# POWERMUX.net
KiCad netlist of a schematic drawn in Altium Designer
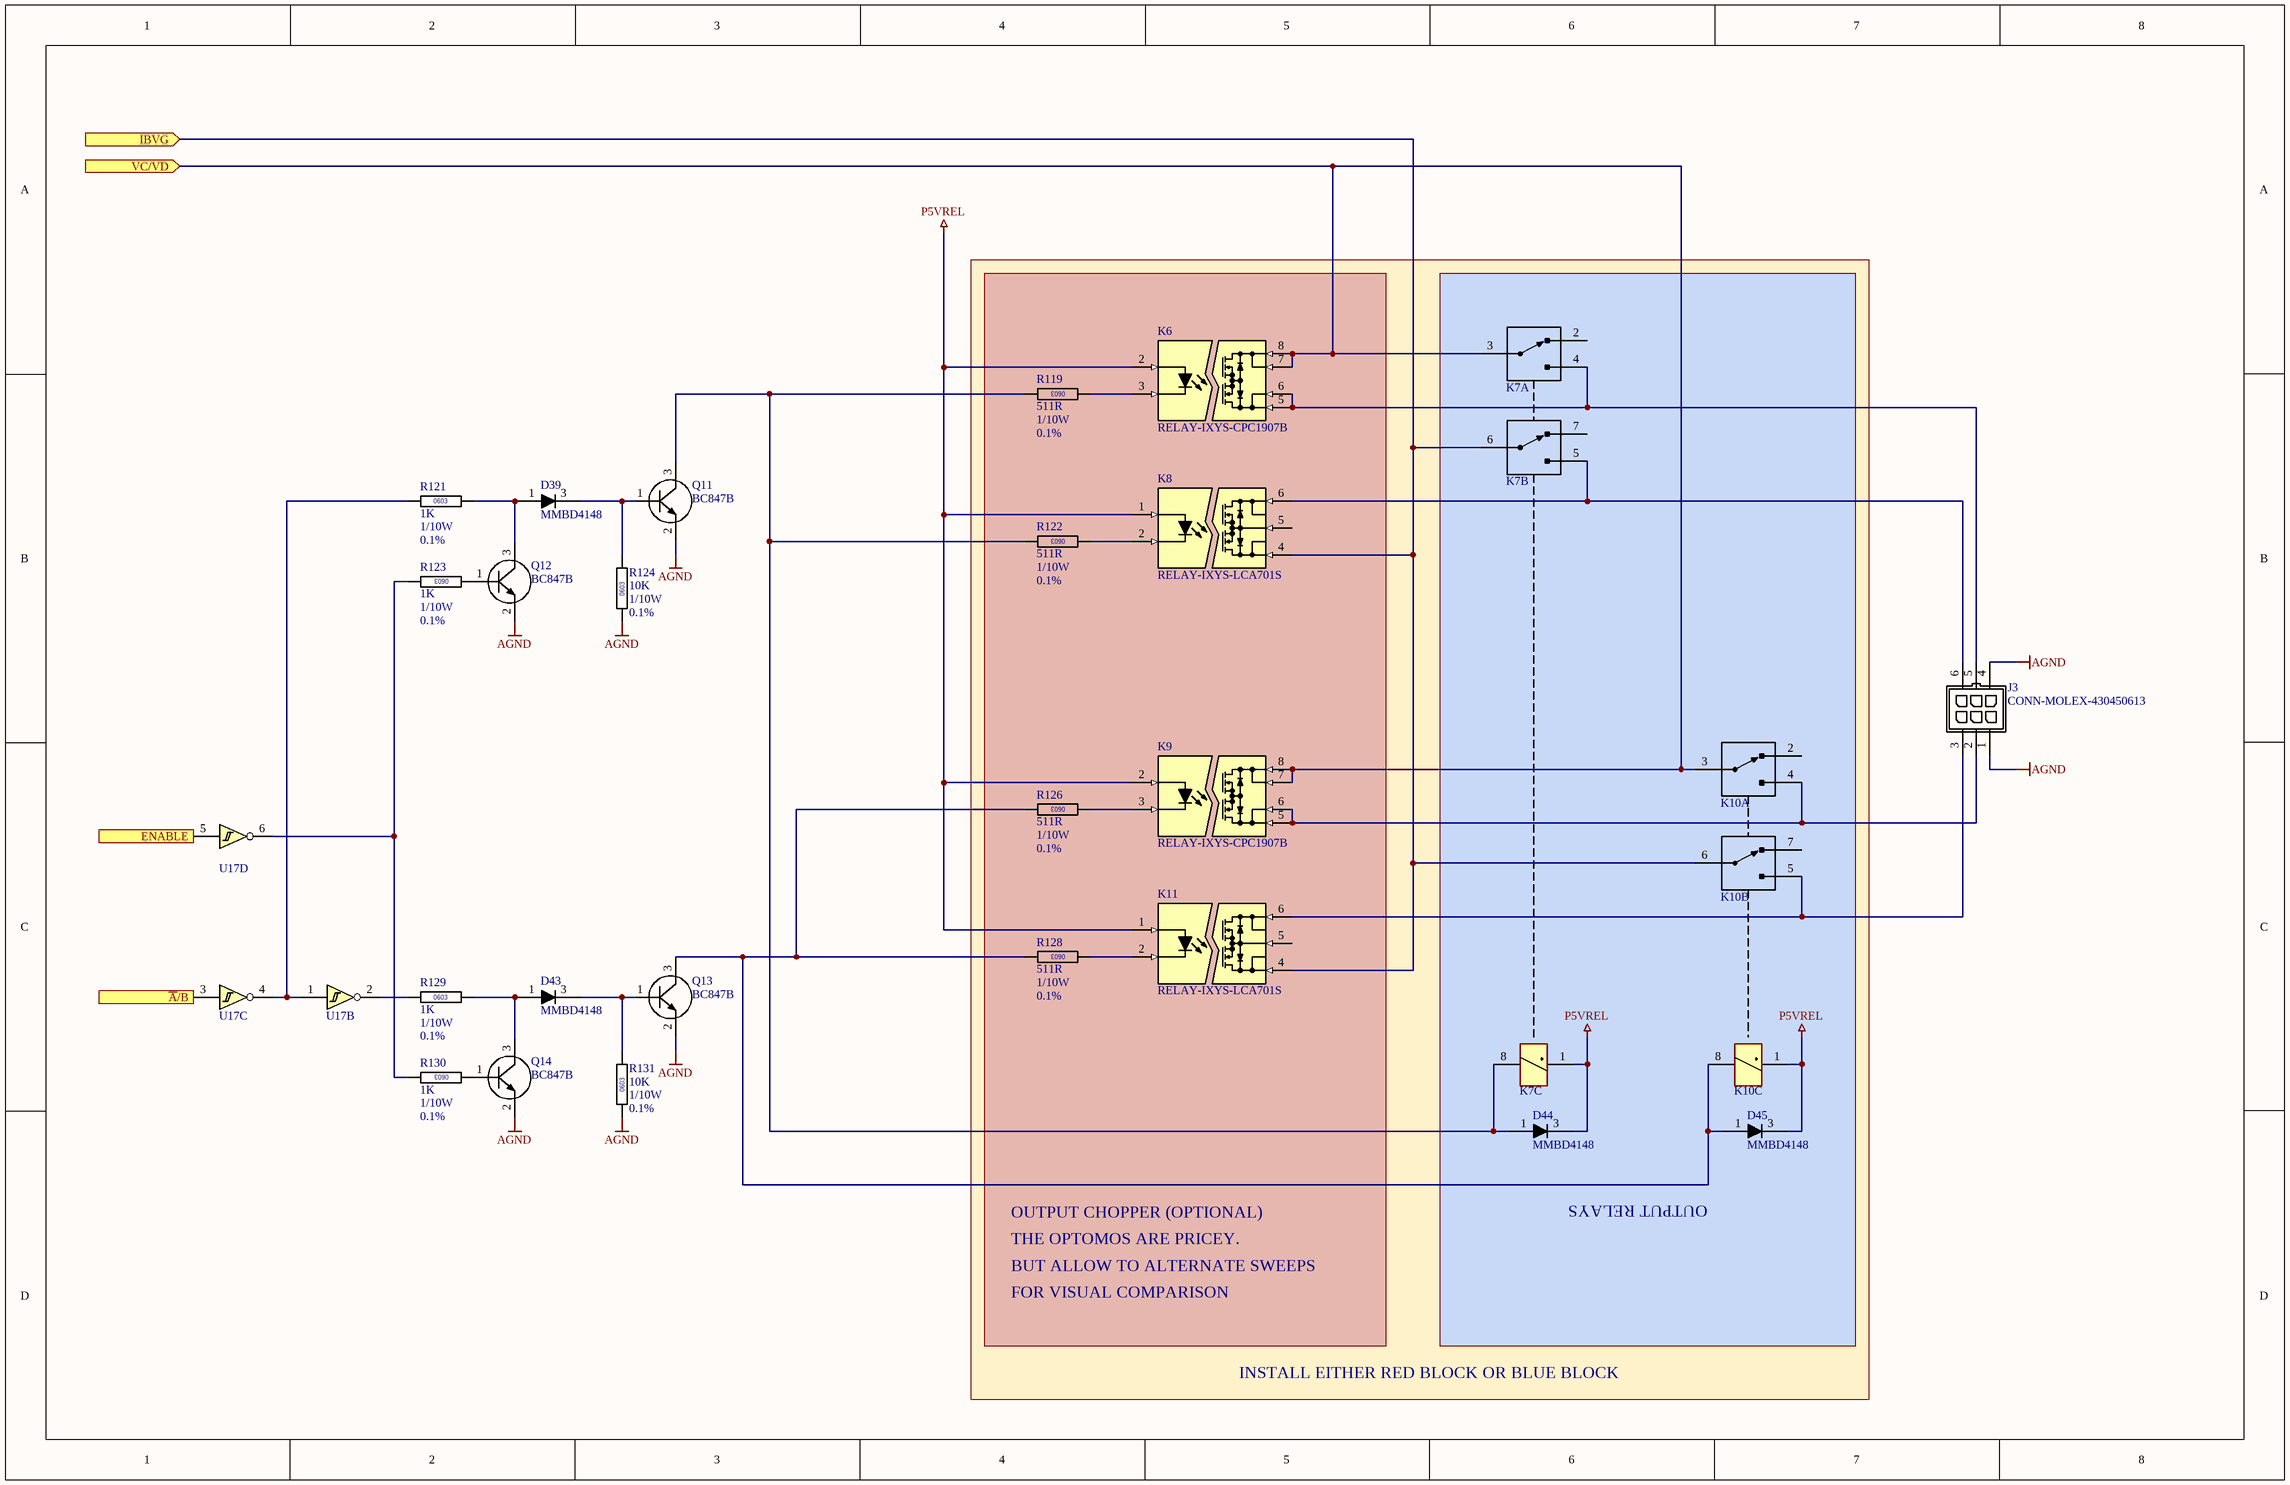
[diagram p0: POWERMUX.SchDoc]

(export (version "E")
  (design (tool "Eeschema 10.0.6"))
  (components
    (comp (ref "D39")
      (value "MMBD4148")
      (description "DIODE,RECTIFIER,75V,0.3A,MMBD4148,SOT23")
      (libsource (lib "DIODES") (part "DIODE-RECTIFIER-DIODES-MMBD4148-SOT23"))
    )
    (comp (ref "D43")
      (value "MMBD4148")
      (description "DIODE,RECTIFIER,75V,0.3A,MMBD4148,SOT23")
      (libsource (lib "DIODES") (part "DIODE-RECTIFIER-DIODES-MMBD4148-SOT23"))
    )
    (comp (ref "D44")
      (value "MMBD4148")
      (description "DIODE,RECTIFIER,75V,0.3A,MMBD4148,SOT23")
      (libsource (lib "DIODES") (part "DIODE-RECTIFIER-DIODES-MMBD4148-SOT23"))
    )
    (comp (ref "D45")
      (value "MMBD4148")
      (description "DIODE,RECTIFIER,75V,0.3A,MMBD4148,SOT23")
      (libsource (lib "DIODES") (part "DIODE-RECTIFIER-DIODES-MMBD4148-SOT23"))
    )
    (comp (ref "J3")
      (value "CONN-MOLEX-430450613")
      (footprint "CONN-MOLEX-430450613")
      (description "CONN,2X3,MOLEX MICROFIT,TH,VERT")
      (libsource (lib "CONNECTORS") (part "CONN-MOLEX-430450613"))
    )
    (comp (ref "K6")
      (value "RELAY-IXYS-CPC1907B")
      (footprint "SO508P1676-8N")
      (description "RELAY,OPTOMOS,6A,60V,AC,IXYS,CPC1907B,SMD")
      (libsource (lib "RELAYS") (part "RELAY-IXYS-CPC1907B"))
    )
    (comp (ref "K7")
      (value "RELAY-KEMET-UA2-5NJ")
      (footprint "RELAY-KEMET-UA2-5NJ")
      (description "RELAY,DPDT,1A,250VAC,220VDC,5V COIL,KEMET,UA2-5NJ")
      (libsource (lib "RELAYS") (part "RELAY-KEMET-UA2-5NJ"))
    )
    (comp (ref "K8")
      (value "RELAY-IXYS-LCA701S")
      (footprint "SO254P960-6N")
      (description "RELAY,OPTOMOS,1.5A,100V,AC,IXYS,LCA701S,SMD")
      (libsource (lib "RELAYS") (part "RELAY-IXYS-LCA701S"))
    )
    (comp (ref "K9")
      (value "RELAY-IXYS-CPC1907B")
      (footprint "SO508P1676-8N")
      (description "RELAY,OPTOMOS,6A,60V,AC,IXYS,CPC1907B,SMD")
      (libsource (lib "RELAYS") (part "RELAY-IXYS-CPC1907B"))
    )
    (comp (ref "K10")
      (value "RELAY-KEMET-UA2-5NJ")
      (footprint "RELAY-KEMET-UA2-5NJ")
      (description "RELAY,DPDT,1A,250VAC,220VDC,5V COIL,KEMET,UA2-5NJ")
      (libsource (lib "RELAYS") (part "RELAY-KEMET-UA2-5NJ"))
    )
    (comp (ref "K11")
      (value "RELAY-IXYS-LCA701S")
      (footprint "SO254P960-6N")
      (description "RELAY,OPTOMOS,1.5A,100V,AC,IXYS,LCA701S,SMD")
      (libsource (lib "RELAYS") (part "RELAY-IXYS-LCA701S"))
    )
    (comp (ref "Q11")
      (value "BC847B")
      (footprint "SOT23")
      (description "XSTR,NPN,45V,0.1A,,BC847B,SOT23")
      (libsource (lib "TRANSISTORS") (part "XSTR-NPN-BC847"))
    )
    (comp (ref "Q12")
      (value "BC847B")
      (footprint "SOT23")
      (description "XSTR,NPN,45V,0.1A,,BC847B,SOT23")
      (libsource (lib "TRANSISTORS") (part "XSTR-NPN-BC847"))
    )
    (comp (ref "Q13")
      (value "BC847B")
      (footprint "SOT23")
      (description "XSTR,NPN,45V,0.1A,,BC847B,SOT23")
      (libsource (lib "TRANSISTORS") (part "XSTR-NPN-BC847"))
    )
    (comp (ref "Q14")
      (value "BC847B")
      (footprint "SOT23")
      (description "XSTR,NPN,45V,0.1A,,BC847B,SOT23")
      (libsource (lib "TRANSISTORS") (part "XSTR-NPN-BC847"))
    )
    (comp (ref "R119")
      (value "511R")
      (footprint "RESC0603")
      (description "RESISTOR,511R,0.1%,100mW,0603 (1608)")
      (fields
        (field (name "POWER") "1/10W")
        (field (name "TOLERANCE") "0.1%")
        (field (name "Comment") "RESC0603")
      )
      (libsource (lib "RESISTORS") (part "RESC-0603-511R-0.1%-1/10W"))
    )
    (comp (ref "R121")
      (value "1K")
      (footprint "RESC0603")
      (description "RESISTOR,1K,0.1%,100mW,0603 (1608)")
      (fields
        (field (name "POWER") "1/10W")
        (field (name "TOLERANCE") "0.1%")
        (field (name "Comment") "RESC0603")
      )
      (libsource (lib "RESISTORS") (part "RESC-0603-1K-0.1%-1/10W"))
    )
    (comp (ref "R122")
      (value "511R")
      (footprint "RESC0603")
      (description "RESISTOR,511R,0.1%,100mW,0603 (1608)")
      (fields
        (field (name "POWER") "1/10W")
        (field (name "TOLERANCE") "0.1%")
        (field (name "Comment") "RESC0603")
      )
      (libsource (lib "RESISTORS") (part "RESC-0603-511R-0.1%-1/10W"))
    )
    (comp (ref "R123")
      (value "1K")
      (footprint "RESC0603")
      (description "RESISTOR,1K,0.1%,100mW,0603 (1608)")
      (fields
        (field (name "POWER") "1/10W")
        (field (name "TOLERANCE") "0.1%")
        (field (name "Comment") "RESC0603")
      )
      (libsource (lib "RESISTORS") (part "RESC-0603-1K-0.1%-1/10W"))
    )
    (comp (ref "R124")
      (value "10K")
      (footprint "RESC0603")
      (description "RESISTOR,10K,0.1%,100mW,0603 (1608)")
      (fields
        (field (name "POWER") "1/10W")
        (field (name "TOLERANCE") "0.1%")
        (field (name "Comment") "RESC0603")
      )
      (libsource (lib "RESISTORS") (part "RESC-0603-10K-0.1%-1/10W"))
    )
    (comp (ref "R126")
      (value "511R")
      (footprint "RESC0603")
      (description "RESISTOR,511R,0.1%,100mW,0603 (1608)")
      (fields
        (field (name "POWER") "1/10W")
        (field (name "TOLERANCE") "0.1%")
        (field (name "Comment") "RESC0603")
      )
      (libsource (lib "RESISTORS") (part "RESC-0603-511R-0.1%-1/10W"))
    )
    (comp (ref "R128")
      (value "511R")
      (footprint "RESC0603")
      (description "RESISTOR,511R,0.1%,100mW,0603 (1608)")
      (fields
        (field (name "POWER") "1/10W")
        (field (name "TOLERANCE") "0.1%")
        (field (name "Comment") "RESC0603")
      )
      (libsource (lib "RESISTORS") (part "RESC-0603-511R-0.1%-1/10W"))
    )
    (comp (ref "R129")
      (value "1K")
      (footprint "RESC0603")
      (description "RESISTOR,1K,0.1%,100mW,0603 (1608)")
      (fields
        (field (name "POWER") "1/10W")
        (field (name "TOLERANCE") "0.1%")
        (field (name "Comment") "RESC0603")
      )
      (libsource (lib "RESISTORS") (part "RESC-0603-1K-0.1%-1/10W"))
    )
    (comp (ref "R130")
      (value "1K")
      (footprint "RESC0603")
      (description "RESISTOR,1K,0.1%,100mW,0603 (1608)")
      (fields
        (field (name "POWER") "1/10W")
        (field (name "TOLERANCE") "0.1%")
        (field (name "Comment") "RESC0603")
      )
      (libsource (lib "RESISTORS") (part "RESC-0603-1K-0.1%-1/10W"))
    )
    (comp (ref "R131")
      (value "10K")
      (footprint "RESC0603")
      (description "RESISTOR,10K,0.1%,100mW,0603 (1608)")
      (fields
        (field (name "POWER") "1/10W")
        (field (name "TOLERANCE") "0.1%")
        (field (name "Comment") "RESC0603")
      )
      (libsource (lib "RESISTORS") (part "RESC-0603-10K-0.1%-1/10W"))
    )
    (comp (ref "U17")
      (value "IC-TI-74HC14")
      (footprint "SOT23-6")
      (description "IC,NOT,HEX,SCHMITTTRIGGER,ONSEMI,MC74AC14DR2G,SO14")
      (libsource (lib "IC-74XX") (part "IC-TI-74HC14-SO14"))
    )
  )
  (nets
    (net (code "1") (name "/ENABLE") (class "Default")
      (node (ref "U17") (pin "5") (pinfunction "5_5") (pintype "passive"))
    )
    (net (code "2") (name "/IBVG") (class "Default")
      (node (ref "K10") (pin "6") (pinfunction "COM_6") (pintype "passive"))
      (node (ref "K11") (pin "4") (pinfunction "4_4") (pintype "input"))
      (node (ref "K7") (pin "6") (pinfunction "COM_6") (pintype "passive"))
      (node (ref "K8") (pin "4") (pinfunction "4_4") (pintype "input"))
    )
    (net (code "3") (name "/VC{slash}VD") (class "Default")
      (node (ref "K10") (pin "3") (pinfunction "COM_3") (pintype "passive"))
      (node (ref "K6") (pin "7") (pinfunction "7_7") (pintype "input"))
      (node (ref "K6") (pin "8") (pinfunction "8_8") (pintype "input"))
      (node (ref "K7") (pin "3") (pinfunction "COM_3") (pintype "passive"))
      (node (ref "K9") (pin "7") (pinfunction "7_7") (pintype "input"))
      (node (ref "K9") (pin "8") (pinfunction "8_8") (pintype "input"))
    )
    (net (code "4") (name "/~{A}{slash}B") (class "Default")
      (node (ref "U17") (pin "3") (pinfunction "3_3") (pintype "passive"))
    )
    (net (code "5") (name "AGND") (class "Default")
      (node (ref "J3") (pin "1") (pinfunction "1_1") (pintype "passive"))
      (node (ref "J3") (pin "4") (pinfunction "4_4") (pintype "passive"))
      (node (ref "Q11") (pin "2") (pinfunction "E_2") (pintype "passive"))
      (node (ref "Q12") (pin "2") (pinfunction "E_2") (pintype "passive"))
      (node (ref "Q13") (pin "2") (pinfunction "E_2") (pintype "passive"))
      (node (ref "Q14") (pin "2") (pinfunction "E_2") (pintype "passive"))
      (node (ref "R124") (pin "2") (pintype "passive"))
      (node (ref "R131") (pin "2") (pintype "passive"))
    )
    (net (code "6") (name "Net-(D39-A)") (class "Default")
      (node (ref "D39") (pin "1") (pinfunction "A_1") (pintype "passive"))
      (node (ref "Q12") (pin "3") (pinfunction "C_3") (pintype "passive"))
      (node (ref "R121") (pin "1") (pintype "passive"))
    )
    (net (code "7") (name "Net-(D39-K)") (class "Default")
      (node (ref "D39") (pin "3") (pinfunction "K_3") (pintype "passive"))
      (node (ref "Q11") (pin "1") (pinfunction "B_1") (pintype "passive"))
      (node (ref "R124") (pin "1") (pintype "passive"))
    )
    (net (code "8") (name "Net-(D43-A)") (class "Default")
      (node (ref "D43") (pin "1") (pinfunction "A_1") (pintype "passive"))
      (node (ref "Q14") (pin "3") (pinfunction "C_3") (pintype "passive"))
      (node (ref "R129") (pin "1") (pintype "passive"))
    )
    (net (code "9") (name "Net-(D43-K)") (class "Default")
      (node (ref "D43") (pin "3") (pinfunction "K_3") (pintype "passive"))
      (node (ref "Q13") (pin "1") (pinfunction "B_1") (pintype "passive"))
      (node (ref "R131") (pin "1") (pintype "passive"))
    )
    (net (code "10") (name "Net-(D44-A)") (class "Default")
      (node (ref "D44") (pin "1") (pinfunction "A_1") (pintype "passive"))
      (node (ref "K7") (pin "8") (pinfunction "8_8") (pintype "passive"))
      (node (ref "Q11") (pin "3") (pinfunction "C_3") (pintype "passive"))
      (node (ref "R119") (pin "1") (pintype "passive"))
      (node (ref "R122") (pin "1") (pintype "passive"))
    )
    (net (code "11") (name "Net-(D45-A)") (class "Default")
      (node (ref "D45") (pin "1") (pinfunction "A_1") (pintype "passive"))
      (node (ref "K10") (pin "8") (pinfunction "8_8") (pintype "passive"))
      (node (ref "Q13") (pin "3") (pinfunction "C_3") (pintype "passive"))
      (node (ref "R126") (pin "1") (pintype "passive"))
      (node (ref "R128") (pin "1") (pintype "passive"))
    )
    (net (code "12") (name "Net-(K6-Pad3)") (class "Default")
      (node (ref "K6") (pin "3") (pinfunction "3_3") (pintype "input"))
      (node (ref "R119") (pin "2") (pintype "passive"))
    )
    (net (code "13") (name "Net-(K7A-NO)") (class "Default")
      (node (ref "J3") (pin "5") (pinfunction "5_5") (pintype "passive"))
      (node (ref "K6") (pin "5") (pinfunction "5_5") (pintype "input"))
      (node (ref "K6") (pin "6") (pinfunction "6_6") (pintype "input"))
      (node (ref "K7") (pin "4") (pinfunction "NO_4") (pintype "passive"))
    )
    (net (code "14") (name "Net-(K7B-NO)") (class "Default")
      (node (ref "J3") (pin "6") (pinfunction "6_6") (pintype "passive"))
      (node (ref "K7") (pin "5") (pinfunction "NO_5") (pintype "passive"))
      (node (ref "K8") (pin "6") (pinfunction "6_6") (pintype "input"))
    )
    (net (code "15") (name "Net-(K8-Pad2)") (class "Default")
      (node (ref "K8") (pin "2") (pinfunction "2_2") (pintype "input"))
      (node (ref "R122") (pin "2") (pintype "passive"))
    )
    (net (code "16") (name "Net-(K9-Pad3)") (class "Default")
      (node (ref "K9") (pin "3") (pinfunction "3_3") (pintype "input"))
      (node (ref "R126") (pin "2") (pintype "passive"))
    )
    (net (code "17") (name "Net-(K10A-NO)") (class "Default")
      (node (ref "J3") (pin "2") (pinfunction "2_2") (pintype "passive"))
      (node (ref "K10") (pin "4") (pinfunction "NO_4") (pintype "passive"))
      (node (ref "K9") (pin "5") (pinfunction "5_5") (pintype "input"))
      (node (ref "K9") (pin "6") (pinfunction "6_6") (pintype "input"))
    )
    (net (code "18") (name "Net-(K10B-NO)") (class "Default")
      (node (ref "J3") (pin "3") (pinfunction "3_3") (pintype "passive"))
      (node (ref "K10") (pin "5") (pinfunction "NO_5") (pintype "passive"))
      (node (ref "K11") (pin "6") (pinfunction "6_6") (pintype "input"))
    )
    (net (code "19") (name "Net-(K11-Pad2)") (class "Default")
      (node (ref "K11") (pin "2") (pinfunction "2_2") (pintype "input"))
      (node (ref "R128") (pin "2") (pintype "passive"))
    )
    (net (code "20") (name "Net-(Q12-B)") (class "Default")
      (node (ref "Q12") (pin "1") (pinfunction "B_1") (pintype "passive"))
      (node (ref "R123") (pin "2") (pintype "passive"))
    )
    (net (code "21") (name "Net-(Q14-B)") (class "Default")
      (node (ref "Q14") (pin "1") (pinfunction "B_1") (pintype "passive"))
      (node (ref "R130") (pin "2") (pintype "passive"))
    )
    (net (code "22") (name "Net-(R121-Pad2)") (class "Default")
      (node (ref "R121") (pin "2") (pintype "passive"))
      (node (ref "U17") (pin "1") (pinfunction "1_1") (pintype "passive"))
      (node (ref "U17") (pin "4") (pinfunction "4_4") (pintype "passive"))
    )
    (net (code "23") (name "Net-(R123-Pad1)") (class "Default")
      (node (ref "R123") (pin "1") (pintype "passive"))
      (node (ref "R130") (pin "1") (pintype "passive"))
      (node (ref "U17") (pin "6") (pinfunction "6_6") (pintype "passive"))
    )
    (net (code "24") (name "Net-(R129-Pad2)") (class "Default")
      (node (ref "R129") (pin "2") (pintype "passive"))
      (node (ref "U17") (pin "2") (pinfunction "2_2") (pintype "passive"))
    )
    (net (code "25") (name "P5VREL") (class "Default")
      (node (ref "D44") (pin "3") (pinfunction "K_3") (pintype "passive"))
      (node (ref "D45") (pin "3") (pinfunction "K_3") (pintype "passive"))
      (node (ref "K10") (pin "1") (pinfunction "1_1") (pintype "passive"))
      (node (ref "K11") (pin "1") (pinfunction "1_1") (pintype "input"))
      (node (ref "K6") (pin "2") (pinfunction "2_2") (pintype "input"))
      (node (ref "K7") (pin "1") (pinfunction "1_1") (pintype "passive"))
      (node (ref "K8") (pin "1") (pinfunction "1_1") (pintype "input"))
      (node (ref "K9") (pin "2") (pinfunction "2_2") (pintype "input"))
    )
    (net (code "26") (name "unconnected-(K7A-NC-Pad2)") (class "Default")
      (node (ref "K7") (pin "2") (pinfunction "NC_2") (pintype "passive"))
    )
    (net (code "27") (name "unconnected-(K7B-NC-Pad7)") (class "Default")
      (node (ref "K7") (pin "7") (pinfunction "NC_7") (pintype "passive"))
    )
    (net (code "28") (name "unconnected-(K8-Pad5)") (class "Default")
      (node (ref "K8") (pin "5") (pinfunction "5_5") (pintype "input"))
    )
    (net (code "29") (name "unconnected-(K10A-NC-Pad2)") (class "Default")
      (node (ref "K10") (pin "2") (pinfunction "NC_2") (pintype "passive"))
    )
    (net (code "30") (name "unconnected-(K10B-NC-Pad7)") (class "Default")
      (node (ref "K10") (pin "7") (pinfunction "NC_7") (pintype "passive"))
    )
    (net (code "31") (name "unconnected-(K11-Pad5)") (class "Default")
      (node (ref "K11") (pin "5") (pinfunction "5_5") (pintype "input"))
    )
  )
)
